# Game_Consol_Power.net
KiCad netlist of a schematic drawn in Altium Designer
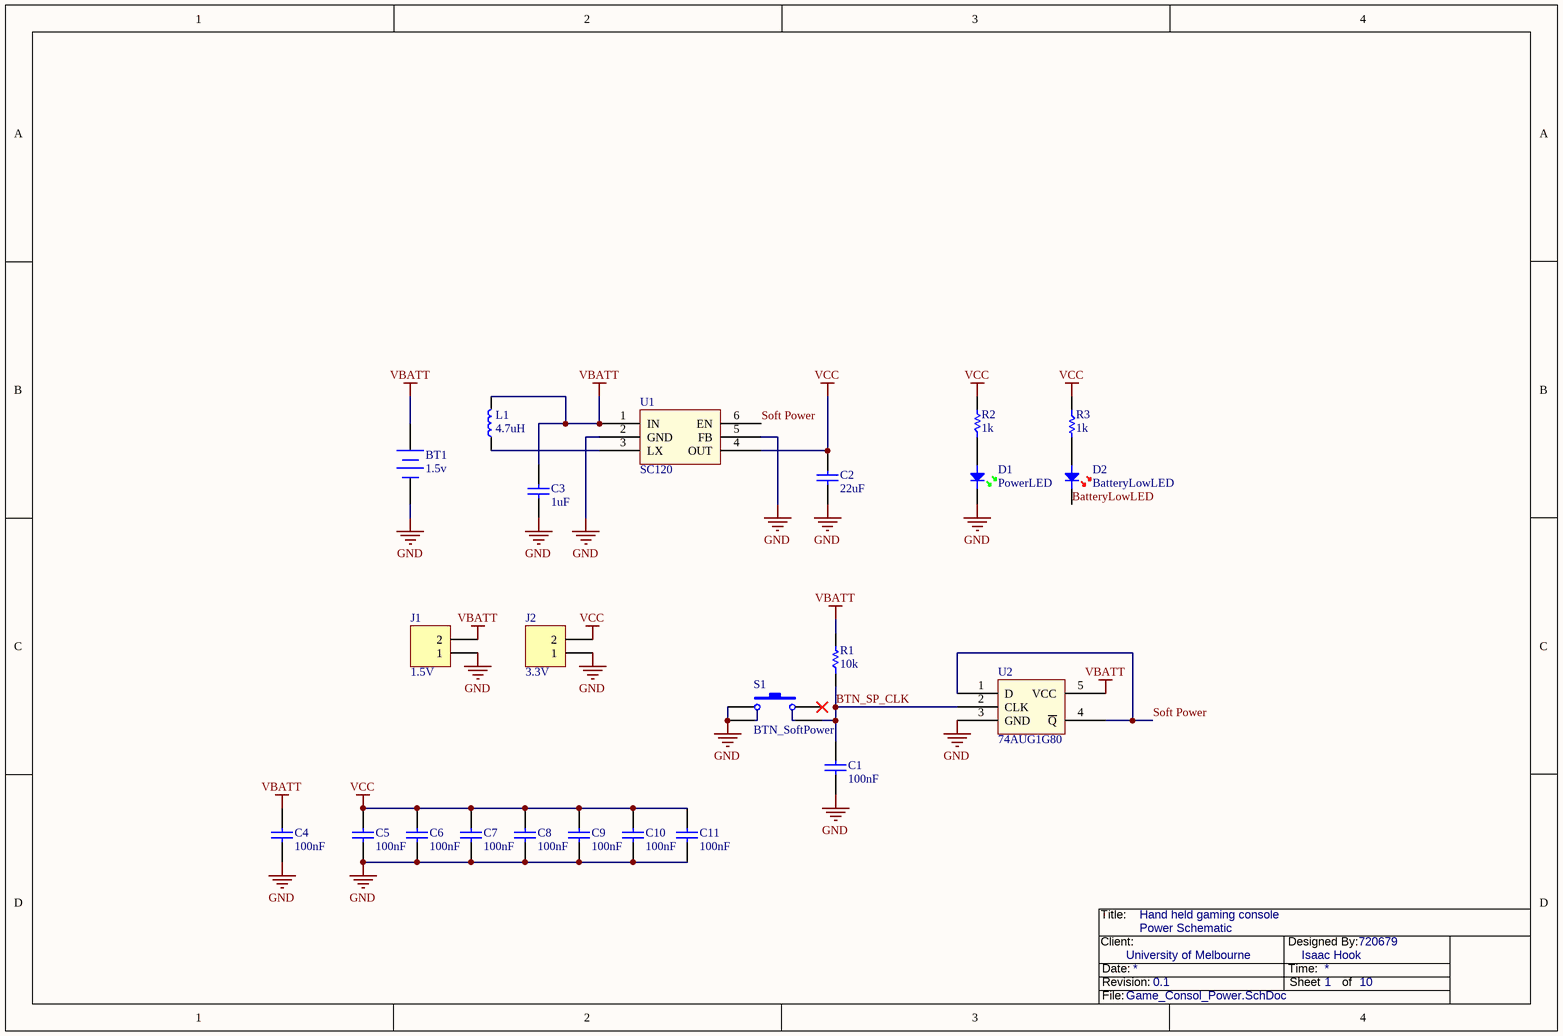
[diagram p0: Game_Consol_Power.SchDoc]

(export (version "E")
  (design (tool "Eeschema 10.0.6"))
  (components
    (comp (ref "BT1")
      (value "1.5v")
      (footprint "BATT_HOLDER")
      (description "Battery Holder AA 1.5v")
      (fields (field (name "PUBLISHER") "Altium Limited"))
      (libsource (lib "EmbSD Lib 0v1") (part "BAT"))
    )
    (comp (ref "C1")
      (value "100nF")
      (footprint "0805")
      (description "Capacitor 100nF")
      (libsource (lib "EmbSD Lib 0v1") (part "C 0805"))
    )
    (comp (ref "C2")
      (value "22uF")
      (footprint "1210")
      (description "Capacitor 22uF")
      (fields
        (field (name "MANUFACTURER") "Generic Components")
        (field (name "MANUFACTURER PART NUMBER") "LMK316F226ZL-T")
        (field (name "PUBLISHER") "Altium Limited")
      )
      (libsource (lib "EmbSD Lib 0v1") (part "C 1210"))
    )
    (comp (ref "C3")
      (value "1uF")
      (footprint "0805")
      (description "Capacitor 100nF")
      (libsource (lib "EmbSD Lib 0v1") (part "C 0805"))
    )
    (comp (ref "C4")
      (value "100nF")
      (footprint "0805")
      (description "Capacitor 100nF")
      (libsource (lib "EmbSD Lib 0v1") (part "C 0805"))
    )
    (comp (ref "C5")
      (value "100nF")
      (footprint "0805")
      (description "Capacitor 100nF")
      (libsource (lib "EmbSD Lib 0v1") (part "C 0805"))
    )
    (comp (ref "C6")
      (value "100nF")
      (footprint "0805")
      (description "Capacitor 100nF")
      (libsource (lib "EmbSD Lib 0v1") (part "C 0805"))
    )
    (comp (ref "C7")
      (value "100nF")
      (footprint "0805")
      (description "Capacitor 100nF")
      (libsource (lib "EmbSD Lib 0v1") (part "C 0805"))
    )
    (comp (ref "C8")
      (value "100nF")
      (footprint "0805")
      (description "Capacitor 100nF")
      (libsource (lib "EmbSD Lib 0v1") (part "C 0805"))
    )
    (comp (ref "C9")
      (value "100nF")
      (footprint "0805")
      (description "Capacitor 100nF")
      (libsource (lib "EmbSD Lib 0v1") (part "C 0805"))
    )
    (comp (ref "C10")
      (value "100nF")
      (footprint "0805")
      (description "Capacitor 100nF")
      (libsource (lib "EmbSD Lib 0v1") (part "C 0805"))
    )
    (comp (ref "C11")
      (value "100nF")
      (footprint "0805")
      (description "Capacitor 100nF")
      (libsource (lib "EmbSD Lib 0v1") (part "C 0805"))
    )
    (comp (ref "D1")
      (value "PowerLED")
      (footprint "0805D")
      (description "Light Emitting Diode")
      (fields (field (name "MANUFACTURER") "Generic Components") (field (name "PUBLISHER") "Altium Limited"))
      (libsource (lib "EmbSD Lib 0v1") (part "LED GREEN"))
    )
    (comp (ref "D2")
      (value "BatteryLowLED")
      (footprint "0805D")
      (description "Light Emitting Diode")
      (fields (field (name "MANUFACTURER") "Generic Components") (field (name "PUBLISHER") "Altium Limited"))
      (libsource (lib "EmbSD Lib 0v1") (part "LED RED"))
    )
    (comp (ref "J1")
      (value "1.5V")
      (footprint "HDR1X2")
      (description "2 Pin Header")
      (fields (field (name "PUBLISHER") "Altium Limited"))
      (libsource (lib "EmbSD Lib 0v1") (part "HDR2"))
    )
    (comp (ref "J2")
      (value "3.3V")
      (footprint "HDR1X2")
      (description "2 Pin Header")
      (fields (field (name "PUBLISHER") "Altium Limited"))
      (libsource (lib "EmbSD Lib 0v1") (part "HDR2"))
    )
    (comp (ref "L1")
      (value "4.7uH")
      (footprint "1210L")
      (description "Inductor 4.7uH")
      (fields
        (field (name "MANUFACTURER") "Murata Electronics North America")
        (field (name "MANUFACTURER PART NUMBER") "LQH32CN4R7M23L")
        (field (name "PUBLISHER") "Altium Limited")
      )
      (libsource (lib "EmbSD Lib 0v1") (part "I 1210"))
    )
    (comp (ref "R1")
      (value "10k")
      (footprint "0805")
      (description "Resistor")
      (libsource (lib "LineTracer") (part "R"))
    )
    (comp (ref "R2")
      (value "1k")
      (footprint "0805")
      (description "Resistor")
      (libsource (lib "EmbSD Lib 0v1") (part "R"))
    )
    (comp (ref "R3")
      (value "1k")
      (footprint "0805")
      (description "Resistor")
      (libsource (lib "EmbSD Lib 0v1") (part "R"))
    )
    (comp (ref "S1")
      (value "BTN_SoftPower")
      (footprint "SPNO_SMD")
      (description "Push Button Switch")
      (fields
        (field (name "MANUFACTURER") "TE Connectivity")
        (field (name "MANUFACTURER PART NUMBER") "FSM4JSMA")
        (field (name "PUBLISHER") "Altium Limited")
      )
      (libsource (lib "EmbSD Lib 0v1") (part "SW-PB"))
    )
    (comp (ref "U1")
      (value "SC120")
      (footprint "SOT23-6")
      (description "Regulator Low Voltage")
      (libsource (lib "EmbSD Lib 0v1") (part "SC120"))
    )
    (comp (ref "U2")
      (value "74AUG1G80")
      (footprint "SOT23-5")
      (description "Inverted single D flip flop")
      (libsource (lib "EmbSD Lib 0v1") (part "74AUG1G80"))
    )
  )
  (nets
    (net (code "1") (name "/BTN_SP_CLK") (class "Default")
      (node (ref "C1") (pin "1") (pinfunction "1_1") (pintype "passive"))
      (node (ref "R1") (pin "1") (pintype "passive"))
      (node (ref "S1") (pin "4") (pinfunction "4_4") (pintype "passive"))
      (node (ref "U2") (pin "2") (pinfunction "CLK_2") (pintype "passive"))
    )
    (net (code "2") (name "/BatteryLowLED") (class "Default")
      (node (ref "D2") (pin "K") (pinfunction "K_K") (pintype "passive"))
    )
    (net (code "3") (name "/Soft Power") (class "Default")
      (node (ref "U1") (pin "6") (pinfunction "EN_6") (pintype "passive"))
      (node (ref "U2") (pin "1") (pinfunction "D_1") (pintype "passive"))
      (node (ref "U2") (pin "4") (pinfunction "~{Q}_4") (pintype "passive"))
    )
    (net (code "4") (name "GND") (class "Default")
      (node (ref "BT1") (pin "2") (pinfunction "-_2") (pintype "passive"))
      (node (ref "C1") (pin "2") (pinfunction "2_2") (pintype "passive"))
      (node (ref "C10") (pin "1") (pinfunction "1_1") (pintype "passive"))
      (node (ref "C11") (pin "1") (pinfunction "1_1") (pintype "passive"))
      (node (ref "C2") (pin "2") (pinfunction "2_2") (pintype "passive"))
      (node (ref "C3") (pin "1") (pinfunction "1_1") (pintype "passive"))
      (node (ref "C4") (pin "2") (pinfunction "2_2") (pintype "passive"))
      (node (ref "C5") (pin "1") (pinfunction "1_1") (pintype "passive"))
      (node (ref "C6") (pin "1") (pinfunction "1_1") (pintype "passive"))
      (node (ref "C7") (pin "1") (pinfunction "1_1") (pintype "passive"))
      (node (ref "C8") (pin "1") (pinfunction "1_1") (pintype "passive"))
      (node (ref "C9") (pin "1") (pinfunction "1_1") (pintype "passive"))
      (node (ref "D1") (pin "K") (pinfunction "K_K") (pintype "passive"))
      (node (ref "J1") (pin "1") (pinfunction "1_1") (pintype "passive"))
      (node (ref "J2") (pin "1") (pinfunction "1_1") (pintype "passive"))
      (node (ref "S1") (pin "1") (pinfunction "1_1") (pintype "passive"))
      (node (ref "S1") (pin "2") (pinfunction "2_2") (pintype "passive"))
      (node (ref "U1") (pin "2") (pinfunction "GND_2") (pintype "passive"))
      (node (ref "U1") (pin "5") (pinfunction "FB_5") (pintype "passive"))
      (node (ref "U2") (pin "3") (pinfunction "GND_3") (pintype "passive"))
    )
    (net (code "5") (name "Net-(D1-PadA)") (class "Default")
      (node (ref "D1") (pin "A") (pinfunction "A_A") (pintype "passive"))
      (node (ref "R2") (pin "1") (pintype "passive"))
    )
    (net (code "6") (name "Net-(D2-PadA)") (class "Default")
      (node (ref "D2") (pin "A") (pinfunction "A_A") (pintype "passive"))
      (node (ref "R3") (pin "2") (pintype "passive"))
    )
    (net (code "7") (name "Net-(U1-LX)") (class "Default")
      (node (ref "L1") (pin "1") (pinfunction "1_1") (pintype "passive"))
      (node (ref "U1") (pin "3") (pinfunction "LX_3") (pintype "passive"))
    )
    (net (code "8") (name "VBATT") (class "Default")
      (node (ref "BT1") (pin "1") (pinfunction "+_1") (pintype "passive"))
      (node (ref "C3") (pin "2") (pinfunction "2_2") (pintype "passive"))
      (node (ref "C4") (pin "1") (pinfunction "1_1") (pintype "passive"))
      (node (ref "J1") (pin "2") (pinfunction "2_2") (pintype "passive"))
      (node (ref "L1") (pin "2") (pinfunction "2_2") (pintype "passive"))
      (node (ref "R1") (pin "2") (pintype "passive"))
      (node (ref "U1") (pin "1") (pinfunction "IN_1") (pintype "passive"))
      (node (ref "U2") (pin "5") (pinfunction "VCC_5") (pintype "passive"))
    )
    (net (code "9") (name "VCC") (class "Default")
      (node (ref "C10") (pin "2") (pinfunction "2_2") (pintype "passive"))
      (node (ref "C11") (pin "2") (pinfunction "2_2") (pintype "passive"))
      (node (ref "C2") (pin "1") (pinfunction "1_1") (pintype "passive"))
      (node (ref "C5") (pin "2") (pinfunction "2_2") (pintype "passive"))
      (node (ref "C6") (pin "2") (pinfunction "2_2") (pintype "passive"))
      (node (ref "C7") (pin "2") (pinfunction "2_2") (pintype "passive"))
      (node (ref "C8") (pin "2") (pinfunction "2_2") (pintype "passive"))
      (node (ref "C9") (pin "2") (pinfunction "2_2") (pintype "passive"))
      (node (ref "J2") (pin "2") (pinfunction "2_2") (pintype "passive"))
      (node (ref "R2") (pin "2") (pintype "passive"))
      (node (ref "R3") (pin "1") (pintype "passive"))
      (node (ref "U1") (pin "4") (pinfunction "OUT_4") (pintype "passive"))
    )
    (net (code "10") (name "unconnected-(S1-Pad3)") (class "Default")
      (node (ref "S1") (pin "3") (pinfunction "3_3") (pintype "passive+no_connect"))
    )
  )
)
